# Top.net
KiCad netlist of a schematic drawn in Altium Designer
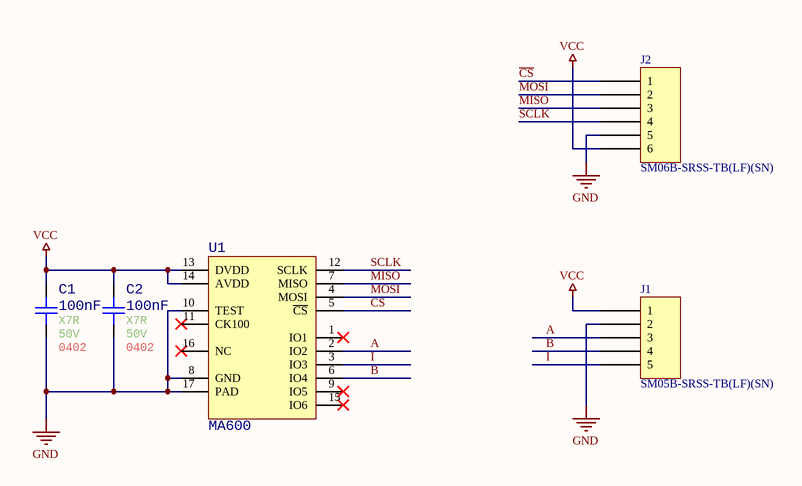
[diagram p0: Top.SchDoc]

(export (version "E")
  (design (tool "Eeschema 10.0.6"))
  (components
    (comp (ref "C1")
      (value "100nF")
      (footprint "Generic 0402 capacitor")
      (fields
        (field (name "TEMPERATURE COEFFICIENT") "X7R")
        (field (name "VOLTAGE RATING") "50V")
        (field (name "CASE/PACKAGE") "0402")
        (field (name "TOLERANCE") "10%")
        (field (name "Comment") "GRT155R71H104KE01D")
      )
      (libsource (lib "Raise Robotics") (part "Unpolarized Capacitor"))
    )
    (comp (ref "C2")
      (value "100nF")
      (footprint "Generic 0402 capacitor")
      (fields
        (field (name "TEMPERATURE COEFFICIENT") "X7R")
        (field (name "VOLTAGE RATING") "50V")
        (field (name "CASE/PACKAGE") "0402")
        (field (name "TOLERANCE") "10%")
        (field (name "Comment") "GRT155R71H104KE01D")
      )
      (libsource (lib "Raise Robotics") (part "Unpolarized Capacitor"))
    )
    (comp (ref "J1")
      (value "SM05B-SRSS-TB(LF)(SN)")
      (footprint "JST SM05B-SRSS-TB")
      (description "CONN HEADER SMD R/A 5POS 1MM")
      (fields (field (name "MANUFACTURER") "JST Sales America Inc."))
      (libsource (lib "Celestial Altium Library - altium_library") (part "5 Pin"))
    )
    (comp (ref "J2")
      (value "SM06B-SRSS-TB(LF)(SN)")
      (footprint "JST SM06B-SRSS-TB")
      (description "CONN HEADER SMD R/A 6POS 1MM")
      (fields (field (name "MANUFACTURER") "JST Sales America Inc."))
      (libsource (lib "Celestial Altium Library - altium_library") (part "6 Pin"))
    )
    (comp (ref "U1")
      (value "MA600")
      (footprint "IC_MA702GQ-Z")
      (description "Hall effect encoder")
      (libsource (lib "IC") (part "MA600"))
    )
  )
  (nets
    (net (code "1") (name "/A") (class "Default")
      (node (ref "J1") (pin "3") (pinfunction "3_3") (pintype "passive"))
      (node (ref "U1") (pin "2") (pinfunction "IO2_2") (pintype "passive"))
    )
    (net (code "2") (name "/B") (class "Default")
      (node (ref "J1") (pin "4") (pinfunction "4_4") (pintype "passive"))
      (node (ref "U1") (pin "6") (pinfunction "IO4_6") (pintype "passive"))
    )
    (net (code "3") (name "/I") (class "Default")
      (node (ref "J1") (pin "5") (pinfunction "5_5") (pintype "passive"))
      (node (ref "U1") (pin "3") (pinfunction "IO3_3") (pintype "passive"))
    )
    (net (code "4") (name "/MISO") (class "Default")
      (node (ref "J2") (pin "3") (pinfunction "3_3") (pintype "passive"))
      (node (ref "U1") (pin "7") (pinfunction "MISO_7") (pintype "passive"))
    )
    (net (code "5") (name "/MOSI") (class "Default")
      (node (ref "J2") (pin "2") (pinfunction "2_2") (pintype "passive"))
      (node (ref "U1") (pin "4") (pinfunction "MOSI_4") (pintype "passive"))
    )
    (net (code "6") (name "/SCLK") (class "Default")
      (node (ref "J2") (pin "4") (pinfunction "4_4") (pintype "passive"))
      (node (ref "U1") (pin "12") (pinfunction "SCLK_12") (pintype "passive"))
    )
    (net (code "7") (name "/~{CS}") (class "Default")
      (node (ref "J2") (pin "1") (pinfunction "1_1") (pintype "passive"))
      (node (ref "U1") (pin "5") (pinfunction "~{CS}_5") (pintype "passive"))
    )
    (net (code "8") (name "GND") (class "Default")
      (node (ref "C1") (pin "1") (pinfunction "1_1") (pintype "passive"))
      (node (ref "C2") (pin "1") (pinfunction "1_1") (pintype "passive"))
      (node (ref "J1") (pin "2") (pinfunction "2_2") (pintype "passive"))
      (node (ref "J2") (pin "5") (pinfunction "5_5") (pintype "passive"))
      (node (ref "U1") (pin "10") (pinfunction "TEST_10") (pintype "passive"))
      (node (ref "U1") (pin "17") (pinfunction "PAD_17") (pintype "passive"))
      (node (ref "U1") (pin "8") (pinfunction "GND_8") (pintype "passive"))
    )
    (net (code "9") (name "VCC") (class "Default")
      (node (ref "C1") (pin "2") (pinfunction "2_2") (pintype "passive"))
      (node (ref "C2") (pin "2") (pinfunction "2_2") (pintype "passive"))
      (node (ref "J1") (pin "1") (pinfunction "1_1") (pintype "passive"))
      (node (ref "J2") (pin "6") (pinfunction "6_6") (pintype "passive"))
      (node (ref "U1") (pin "13") (pinfunction "DVDD_13") (pintype "passive"))
      (node (ref "U1") (pin "14") (pinfunction "AVDD_14") (pintype "passive"))
    )
    (net (code "10") (name "unconnected-(U1-CK100-Pad11)") (class "Default")
      (node (ref "U1") (pin "11") (pinfunction "CK100_11") (pintype "passive+no_connect"))
    )
    (net (code "11") (name "unconnected-(U1-IO1-Pad1)") (class "Default")
      (node (ref "U1") (pin "1") (pinfunction "IO1_1") (pintype "passive+no_connect"))
    )
    (net (code "12") (name "unconnected-(U1-IO5-Pad9)") (class "Default")
      (node (ref "U1") (pin "9") (pinfunction "IO5_9") (pintype "passive+no_connect"))
    )
    (net (code "13") (name "unconnected-(U1-IO6-Pad15)") (class "Default")
      (node (ref "U1") (pin "15") (pinfunction "IO6_15") (pintype "passive+no_connect"))
    )
    (net (code "14") (name "unconnected-(U1-NC-Pad16)") (class "Default")
      (node (ref "U1") (pin "16") (pinfunction "NC_16") (pintype "passive+no_connect"))
    )
  )
)
